# BG_Clip_Stage.net
KiCad netlist of a schematic drawn in Altium Designer
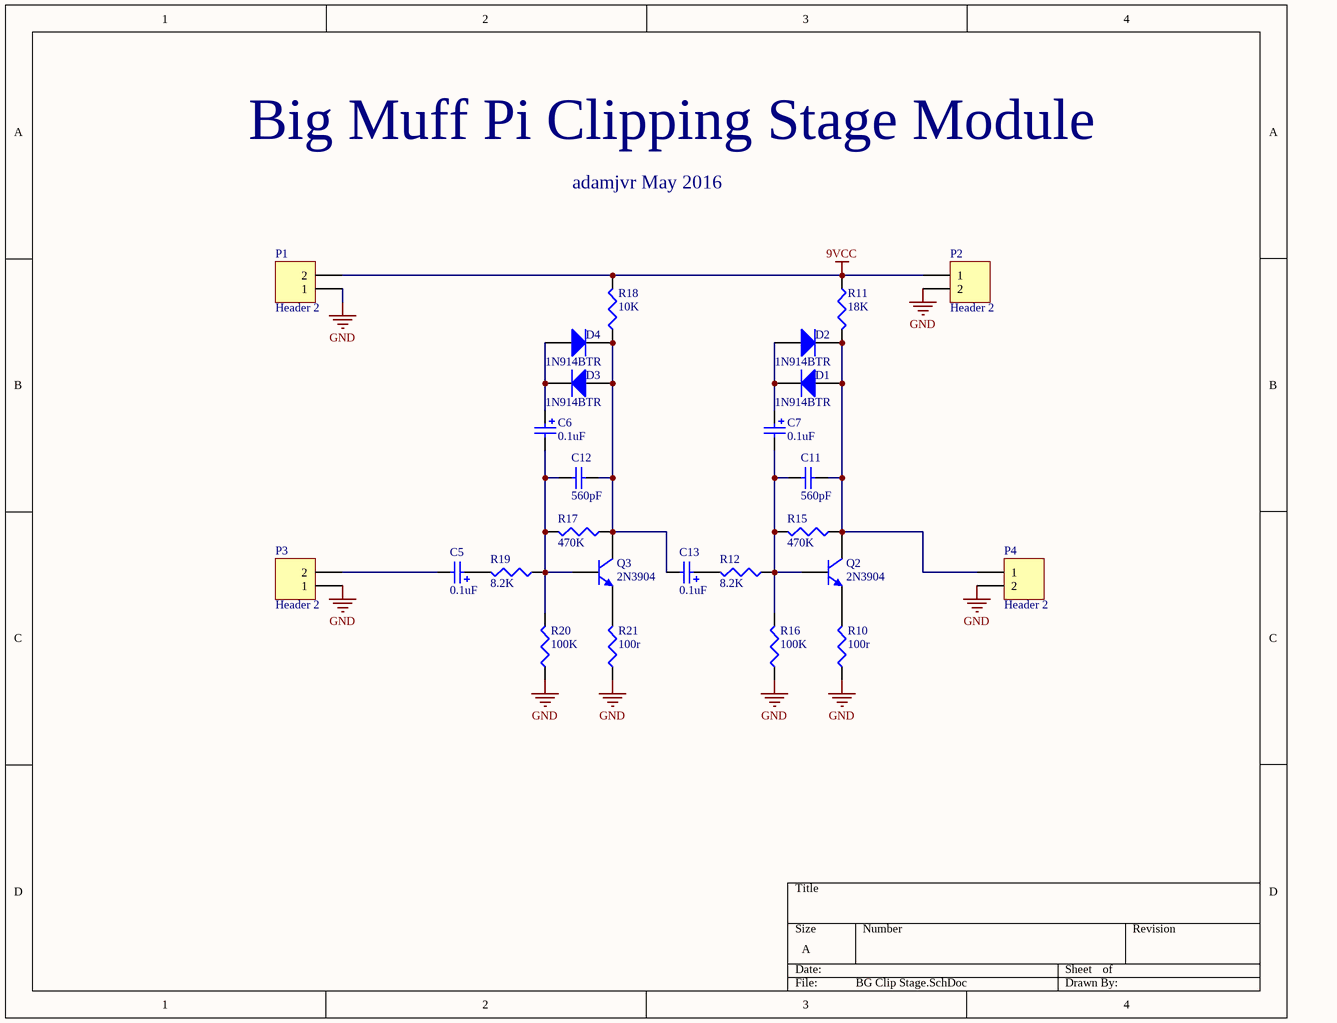
[diagram p0: BG Clip Stage.SchDoc]

(export (version "E")
  (design (tool "Eeschema 10.0.6"))
  (components
    (comp (ref "C5")
      (value "0.1uF")
      (footprint "5X12.5mmCAP")
      (description "CAP ALUM 0.1UF 20% 100V RADIAL")
      (fields
        (field (name "MFR") "Nichicon")
        (field (name "TOLERANCE") "20%")
        (field (name "DESIGNER") "Adam Vadala-Roth")
      )
      (libsource (lib "AudioPartLib") (part "UFG2A0R1MDM1TD"))
    )
    (comp (ref "C6")
      (value "0.1uF")
      (footprint "5X12.5mmCAP")
      (description "CAP ALUM 0.1UF 20% 100V RADIAL")
      (fields
        (field (name "MFR") "Nichicon")
        (field (name "TOLERANCE") "20%")
        (field (name "DESIGNER") "Adam Vadala-Roth")
      )
      (libsource (lib "AudioPartLib") (part "UFG2A0R1MDM1TD"))
    )
    (comp (ref "C7")
      (value "0.1uF")
      (footprint "5X12.5mmCAP")
      (description "CAP ALUM 0.1UF 20% 100V RADIAL")
      (fields
        (field (name "MFR") "Nichicon")
        (field (name "TOLERANCE") "20%")
        (field (name "DESIGNER") "Adam Vadala-Roth")
      )
      (libsource (lib "AudioPartLib") (part "UFG2A0R1MDM1TD"))
    )
    (comp (ref "C11")
      (value "560pF")
      (footprint "C0805")
      (fields
        (field (name "MFR") "Samsung-Electro-Mechanics-America,-Inc.")
        (field (name "TOLERANCE") "5%")
        (field (name "VOLTAGE") "50V")
        (field (name "DESIGNER") "Adam Vadala-Roth")
      )
      (libsource (lib "AudioPartLib") (part "CL21C561JBANNNC"))
    )
    (comp (ref "C12")
      (value "560pF")
      (footprint "C0805")
      (fields
        (field (name "MFR") "Samsung-Electro-Mechanics-America,-Inc.")
        (field (name "TOLERANCE") "5%")
        (field (name "VOLTAGE") "50V")
        (field (name "DESIGNER") "Adam Vadala-Roth")
      )
      (libsource (lib "AudioPartLib") (part "CL21C561JBANNNC"))
    )
    (comp (ref "C13")
      (value "0.1uF")
      (footprint "5X12.5mmCAP")
      (description "CAP ALUM 0.1UF 20% 100V RADIAL")
      (fields
        (field (name "MFR") "Nichicon")
        (field (name "TOLERANCE") "20%")
        (field (name "DESIGNER") "Adam Vadala-Roth")
      )
      (libsource (lib "AudioPartLib") (part "UFG2A0R1MDM1TD"))
    )
    (comp (ref "D1")
      (value "1N914BTR")
      (footprint "DO-35")
      (description "DIODE GEN PURP 100V 200MA DO35")
      (fields
        (field (name "MFR") "Fairchild-Semiconductor")
        (field (name "VOLTAGE") "100V")
        (field (name "DESIGNER") "Adam Vadala-Roth")
      )
      (libsource (lib "AudioPartLib") (part "1N914BTR"))
    )
    (comp (ref "D2")
      (value "1N914BTR")
      (footprint "DO-35")
      (description "DIODE GEN PURP 100V 200MA DO35")
      (fields
        (field (name "MFR") "Fairchild-Semiconductor")
        (field (name "VOLTAGE") "100V")
        (field (name "DESIGNER") "Adam Vadala-Roth")
      )
      (libsource (lib "AudioPartLib") (part "1N914BTR"))
    )
    (comp (ref "D3")
      (value "1N914BTR")
      (footprint "DO-35")
      (description "DIODE GEN PURP 100V 200MA DO35")
      (fields
        (field (name "MFR") "Fairchild-Semiconductor")
        (field (name "VOLTAGE") "100V")
        (field (name "DESIGNER") "Adam Vadala-Roth")
      )
      (libsource (lib "AudioPartLib") (part "1N914BTR"))
    )
    (comp (ref "D4")
      (value "1N914BTR")
      (footprint "DO-35")
      (description "DIODE GEN PURP 100V 200MA DO35")
      (fields
        (field (name "MFR") "Fairchild-Semiconductor")
        (field (name "VOLTAGE") "100V")
        (field (name "DESIGNER") "Adam Vadala-Roth")
      )
      (libsource (lib "AudioPartLib") (part "1N914BTR"))
    )
    (comp (ref "P1")
      (value "Header 2")
      (footprint "HDR1X2")
      (description "Header, 2-Pin")
      (fields (field (name "PUBLISHER") "Altium Limited"))
      (libsource (lib "Miscellaneous Connectors") (part "Header 2"))
    )
    (comp (ref "P2")
      (value "Header 2")
      (footprint "HDR1X2")
      (description "Header, 2-Pin")
      (fields (field (name "PUBLISHER") "Altium Limited"))
      (libsource (lib "") (part "Header 2_1"))
    )
    (comp (ref "P3")
      (value "Header 2")
      (footprint "HDR1X2")
      (description "Header, 2-Pin")
      (fields (field (name "PUBLISHER") "Altium Limited"))
      (libsource (lib "Miscellaneous Connectors") (part "Header 2"))
    )
    (comp (ref "P4")
      (value "Header 2")
      (footprint "HDR1X2")
      (description "Header, 2-Pin")
      (fields (field (name "PUBLISHER") "Altium Limited"))
      (libsource (lib "") (part "Header 2_1"))
    )
    (comp (ref "Q2")
      (value "2N3904")
      (footprint "TO-92A")
      (description "TRANS NPN 40V 0.2A TO-92")
      (fields
        (field (name "MFR") "Fairchild-Semiconductor")
        (field (name "VOLTAGE") "40V")
        (field (name "DESIGNER") "Adam Vadala-Roth")
      )
      (libsource (lib "AudioPartLib") (part "2N3904TF"))
    )
    (comp (ref "Q3")
      (value "2N3904")
      (footprint "TO-92A")
      (description "TRANS NPN 40V 0.2A TO-92")
      (fields
        (field (name "MFR") "Fairchild-Semiconductor")
        (field (name "VOLTAGE") "40V")
        (field (name "DESIGNER") "Adam Vadala-Roth")
      )
      (libsource (lib "AudioPartLib") (part "2N3904TF"))
    )
    (comp (ref "R10")
      (value "100r")
      (footprint "R0805")
      (description "RES SMD 100 OHM 1% 1/8W 0805")
      (fields
        (field (name "MFR") "Vishay-Dale")
        (field (name "TOLERANCE") "1%")
        (field (name "DESIGNER") "Adam Vadala-Roth")
      )
      (libsource (lib "AudioPartLib") (part "CRCW0805100RFKEA"))
    )
    (comp (ref "R11")
      (value "18K")
      (footprint "R0805")
      (description "RES SMD 18K OHM 1% 1/8W 0805")
      (fields
        (field (name "MFR") "Panasonic-Electronic-Components")
        (field (name "TOLERANCE") "1%")
        (field (name "DESIGNER") "Adam Vadala-Roth")
      )
      (libsource (lib "AudioPartLib") (part "ERJ-6ENF1802V"))
    )
    (comp (ref "R12")
      (value "8.2K")
      (footprint "R0805")
      (description "RES SMD 8.2K OHM 1% 1/8W 0805")
      (fields
        (field (name "MFR") "Samsung-Electro-Mechanics-America,-Inc.")
        (field (name "TOLERANCE") "1%")
        (field (name "DESIGNER") "Adam Vadala-Roth")
      )
      (libsource (lib "AudioPartLib") (part "RC2012F822CS"))
    )
    (comp (ref "R15")
      (value "470K")
      (footprint "R0805")
      (description "RES SMD 470K OHM 1% 1/8W 0805")
      (fields
        (field (name "MFR") "Panasonic-Electronic-Components")
        (field (name "TOLERANCE") "1%")
        (field (name "DESIGNER") "Adam Vadala-Roth")
      )
      (libsource (lib "AudioPartLib") (part "ERJ-6ENF4703V"))
    )
    (comp (ref "R16")
      (value "100K")
      (footprint "R0805")
      (description "RES SMD 100K OHM 1% 1/8W 0805")
      (fields
        (field (name "MFR") "Panasonic-Electronic-Components")
        (field (name "TOLERANCE") "1%")
        (field (name "DESIGNER") "Adam Vadala-Roth")
      )
      (libsource (lib "AudioPartLib") (part "ERJ-6ENF1003V"))
    )
    (comp (ref "R17")
      (value "470K")
      (footprint "R0805")
      (description "RES SMD 470K OHM 1% 1/8W 0805")
      (fields
        (field (name "MFR") "Panasonic-Electronic-Components")
        (field (name "TOLERANCE") "1%")
        (field (name "DESIGNER") "Adam Vadala-Roth")
      )
      (libsource (lib "AudioPartLib") (part "ERJ-6ENF4703V"))
    )
    (comp (ref "R18")
      (value "10K")
      (footprint "R0805")
      (description "RES SMD 10K OHM 1% 1/8W 0805")
      (fields
        (field (name "MFR") "Panasonic-Electronic-Components")
        (field (name "TOLERANCE") "1%")
        (field (name "DESIGNER") "Adam Vadala-Roth")
      )
      (libsource (lib "AudioPartLib") (part "ERJ-6ENF1002V"))
    )
    (comp (ref "R19")
      (value "8.2K")
      (footprint "R0805")
      (description "RES SMD 8.2K OHM 1% 1/8W 0805")
      (fields
        (field (name "MFR") "Samsung-Electro-Mechanics-America,-Inc.")
        (field (name "TOLERANCE") "1%")
        (field (name "DESIGNER") "Adam Vadala-Roth")
      )
      (libsource (lib "AudioPartLib") (part "RC2012F822CS"))
    )
    (comp (ref "R20")
      (value "100K")
      (footprint "R0805")
      (description "RES SMD 100K OHM 1% 1/8W 0805")
      (fields
        (field (name "MFR") "Panasonic-Electronic-Components")
        (field (name "TOLERANCE") "1%")
        (field (name "DESIGNER") "Adam Vadala-Roth")
      )
      (libsource (lib "AudioPartLib") (part "ERJ-6ENF1003V"))
    )
    (comp (ref "R21")
      (value "100r")
      (footprint "R0805")
      (description "RES SMD 100 OHM 1% 1/8W 0805")
      (fields
        (field (name "MFR") "Vishay-Dale")
        (field (name "TOLERANCE") "1%")
        (field (name "DESIGNER") "Adam Vadala-Roth")
      )
      (libsource (lib "AudioPartLib") (part "CRCW0805100RFKEA"))
    )
  )
  (nets
    (net (code "1") (name "9VCC") (class "Default")
      (node (ref "P1") (pin "2") (pinfunction "2_2") (pintype "passive"))
      (node (ref "P2") (pin "1") (pinfunction "1_1") (pintype "passive"))
      (node (ref "R11") (pin "1") (pinfunction "1_1") (pintype "passive"))
      (node (ref "R18") (pin "2") (pinfunction "2_2") (pintype "passive"))
    )
    (net (code "2") (name "GND") (class "Default")
      (node (ref "P1") (pin "1") (pinfunction "1_1") (pintype "passive"))
      (node (ref "P2") (pin "2") (pinfunction "2_2") (pintype "passive"))
      (node (ref "P3") (pin "1") (pinfunction "1_1") (pintype "passive"))
      (node (ref "P4") (pin "2") (pinfunction "2_2") (pintype "passive"))
      (node (ref "R10") (pin "1") (pinfunction "1_1") (pintype "passive"))
      (node (ref "R16") (pin "1") (pinfunction "1_1") (pintype "passive"))
      (node (ref "R20") (pin "1") (pinfunction "1_1") (pintype "passive"))
      (node (ref "R21") (pin "1") (pinfunction "1_1") (pintype "passive"))
    )
    (net (code "3") (name "Net-(C5-Pad1)") (class "Default")
      (node (ref "C5") (pin "1") (pinfunction "1_1") (pintype "passive"))
      (node (ref "R19") (pin "2") (pinfunction "2_2") (pintype "passive"))
    )
    (net (code "4") (name "Net-(C5-Pad2)") (class "Default")
      (node (ref "C5") (pin "2") (pinfunction "2_2") (pintype "passive"))
      (node (ref "P3") (pin "2") (pinfunction "2_2") (pintype "passive"))
    )
    (net (code "5") (name "Net-(C13-Pad1)") (class "Default")
      (node (ref "C13") (pin "1") (pinfunction "1_1") (pintype "passive"))
      (node (ref "R12") (pin "2") (pinfunction "2_2") (pintype "passive"))
    )
    (net (code "6") (name "Net-(D1-A)") (class "Default")
      (node (ref "C11") (pin "1") (pinfunction "1_1") (pintype "passive"))
      (node (ref "D1") (pin "1") (pinfunction "A_1") (pintype "passive"))
      (node (ref "D2") (pin "2") (pinfunction "K_2") (pintype "passive"))
      (node (ref "P4") (pin "1") (pinfunction "1_1") (pintype "passive"))
      (node (ref "Q2") (pin "3") (pinfunction "C_3") (pintype "passive"))
      (node (ref "R11") (pin "2") (pinfunction "2_2") (pintype "passive"))
      (node (ref "R15") (pin "1") (pinfunction "1_1") (pintype "passive"))
    )
    (net (code "7") (name "Net-(D1-K)") (class "Default")
      (node (ref "C7") (pin "1") (pinfunction "1_1") (pintype "passive"))
      (node (ref "D1") (pin "2") (pinfunction "K_2") (pintype "passive"))
      (node (ref "D2") (pin "1") (pinfunction "A_1") (pintype "passive"))
    )
    (net (code "8") (name "Net-(D3-A)") (class "Default")
      (node (ref "C12") (pin "1") (pinfunction "1_1") (pintype "passive"))
      (node (ref "C13") (pin "2") (pinfunction "2_2") (pintype "passive"))
      (node (ref "D3") (pin "1") (pinfunction "A_1") (pintype "passive"))
      (node (ref "D4") (pin "2") (pinfunction "K_2") (pintype "passive"))
      (node (ref "Q3") (pin "3") (pinfunction "C_3") (pintype "passive"))
      (node (ref "R17") (pin "1") (pinfunction "1_1") (pintype "passive"))
      (node (ref "R18") (pin "1") (pinfunction "1_1") (pintype "passive"))
    )
    (net (code "9") (name "Net-(D3-K)") (class "Default")
      (node (ref "C6") (pin "1") (pinfunction "1_1") (pintype "passive"))
      (node (ref "D3") (pin "2") (pinfunction "K_2") (pintype "passive"))
      (node (ref "D4") (pin "1") (pinfunction "A_1") (pintype "passive"))
    )
    (net (code "10") (name "Net-(Q2-B)") (class "Default")
      (node (ref "C11") (pin "2") (pinfunction "2_2") (pintype "passive"))
      (node (ref "C7") (pin "2") (pinfunction "2_2") (pintype "passive"))
      (node (ref "Q2") (pin "2") (pinfunction "B_2") (pintype "passive"))
      (node (ref "R12") (pin "1") (pinfunction "1_1") (pintype "passive"))
      (node (ref "R15") (pin "2") (pinfunction "2_2") (pintype "passive"))
      (node (ref "R16") (pin "2") (pinfunction "2_2") (pintype "passive"))
    )
    (net (code "11") (name "Net-(Q2-E)") (class "Default")
      (node (ref "Q2") (pin "1") (pinfunction "E_1") (pintype "passive"))
      (node (ref "R10") (pin "2") (pinfunction "2_2") (pintype "passive"))
    )
    (net (code "12") (name "Net-(Q3-B)") (class "Default")
      (node (ref "C12") (pin "2") (pinfunction "2_2") (pintype "passive"))
      (node (ref "C6") (pin "2") (pinfunction "2_2") (pintype "passive"))
      (node (ref "Q3") (pin "2") (pinfunction "B_2") (pintype "passive"))
      (node (ref "R17") (pin "2") (pinfunction "2_2") (pintype "passive"))
      (node (ref "R19") (pin "1") (pinfunction "1_1") (pintype "passive"))
      (node (ref "R20") (pin "2") (pinfunction "2_2") (pintype "passive"))
    )
    (net (code "13") (name "Net-(Q3-E)") (class "Default")
      (node (ref "Q3") (pin "1") (pinfunction "E_1") (pintype "passive"))
      (node (ref "R21") (pin "2") (pinfunction "2_2") (pintype "passive"))
    )
  )
)
